# PAGE_07-DIGITAL_IO.net
KiCad netlist of a schematic drawn in Altium Designer
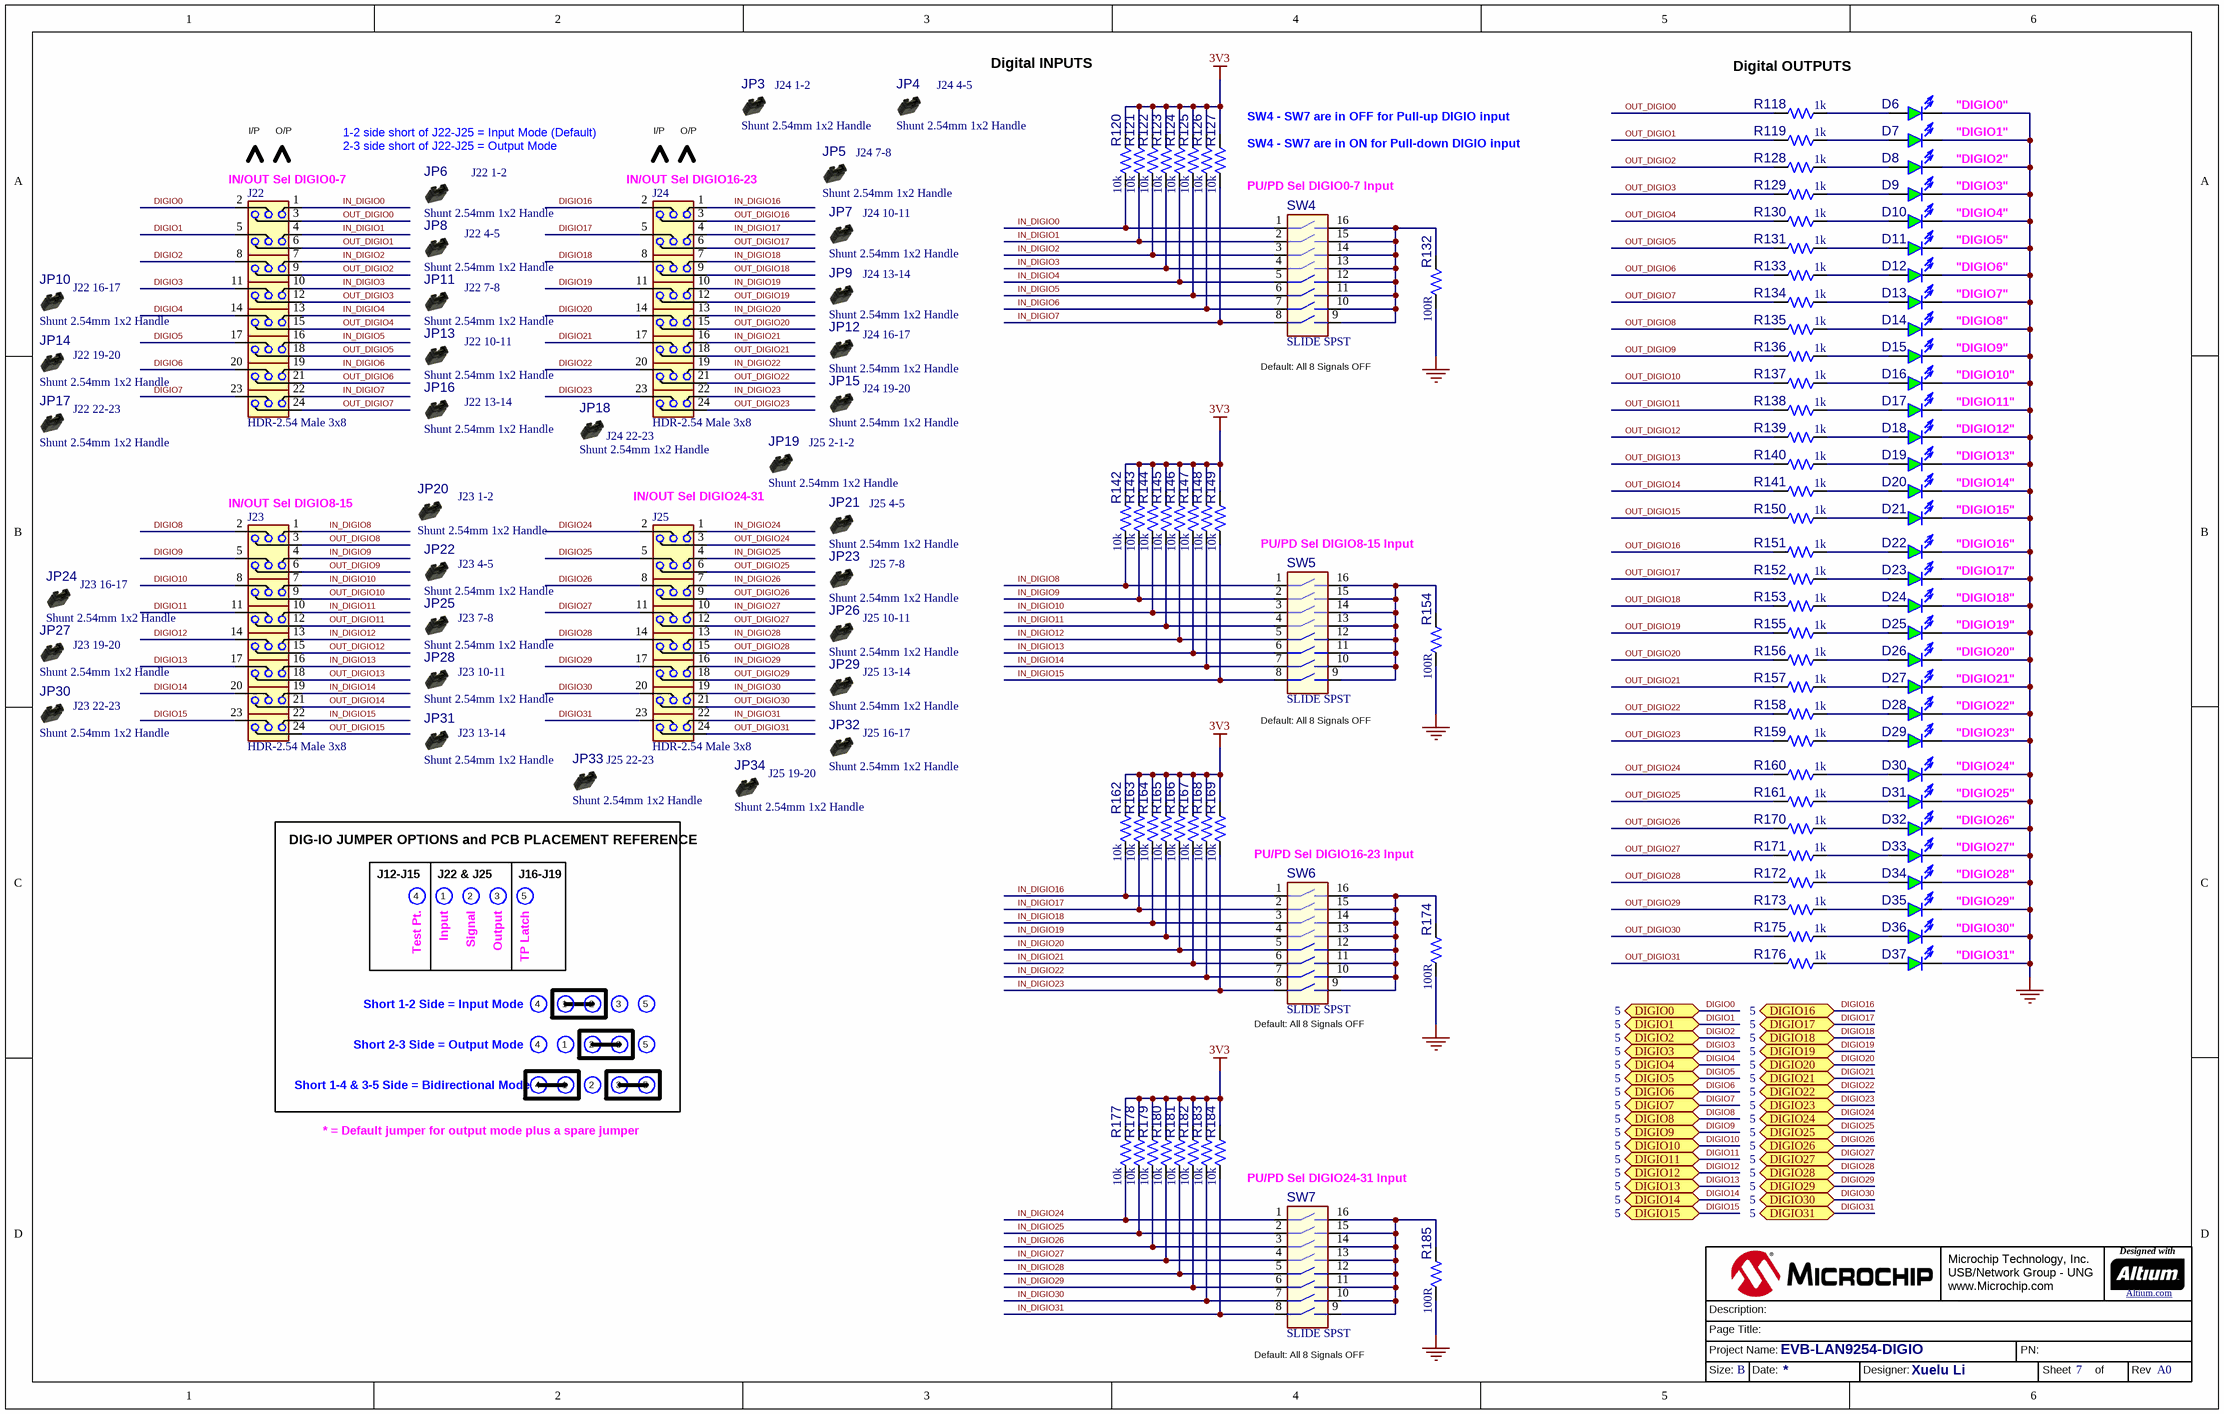
[diagram p0: PAGE 07-DIGITAL IO.SchDoc]

(export (version "E")
  (design (tool "Eeschema 10.0.6"))
  (components
    (comp (ref "D6")
      (value "LED_green")
      (footprint "LED_0603_GREEN")
      (description "LED")
      (fields (field (name "POWER") "75mW") (field (name "OWNER") "Tad Ahlvers"))
      (libsource (lib "MCHP-CDB") (part "LED_green"))
    )
    (comp (ref "D7")
      (value "LED_green")
      (footprint "LED_0603_GREEN")
      (description "LED")
      (fields (field (name "POWER") "75mW") (field (name "OWNER") "Tad Ahlvers"))
      (libsource (lib "MCHP-CDB") (part "LED_green"))
    )
    (comp (ref "D8")
      (value "LED_green")
      (footprint "LED_0603_GREEN")
      (description "LED")
      (fields (field (name "POWER") "75mW") (field (name "OWNER") "Tad Ahlvers"))
      (libsource (lib "MCHP-CDB") (part "LED_green"))
    )
    (comp (ref "D9")
      (value "LED_green")
      (footprint "LED_0603_GREEN")
      (description "LED")
      (fields (field (name "POWER") "75mW") (field (name "OWNER") "Tad Ahlvers"))
      (libsource (lib "MCHP-CDB") (part "LED_green"))
    )
    (comp (ref "D10")
      (value "LED_green")
      (footprint "LED_0603_GREEN")
      (description "LED")
      (fields (field (name "POWER") "75mW") (field (name "OWNER") "Tad Ahlvers"))
      (libsource (lib "MCHP-CDB") (part "LED_green"))
    )
    (comp (ref "D11")
      (value "LED_green")
      (footprint "LED_0603_GREEN")
      (description "LED")
      (fields (field (name "POWER") "75mW") (field (name "OWNER") "Tad Ahlvers"))
      (libsource (lib "MCHP-CDB") (part "LED_green"))
    )
    (comp (ref "D12")
      (value "LED_green")
      (footprint "LED_0603_GREEN")
      (description "LED")
      (fields (field (name "POWER") "75mW") (field (name "OWNER") "Tad Ahlvers"))
      (libsource (lib "MCHP-CDB") (part "LED_green"))
    )
    (comp (ref "D13")
      (value "LED_green")
      (footprint "LED_0603_GREEN")
      (description "LED")
      (fields (field (name "POWER") "75mW") (field (name "OWNER") "Tad Ahlvers"))
      (libsource (lib "MCHP-CDB") (part "LED_green"))
    )
    (comp (ref "D14")
      (value "LED_green")
      (footprint "LED_0603_GREEN")
      (description "LED")
      (fields (field (name "POWER") "75mW") (field (name "OWNER") "Tad Ahlvers"))
      (libsource (lib "MCHP-CDB") (part "LED_green"))
    )
    (comp (ref "D15")
      (value "LED_green")
      (footprint "LED_0603_GREEN")
      (description "LED")
      (fields (field (name "POWER") "75mW") (field (name "OWNER") "Tad Ahlvers"))
      (libsource (lib "MCHP-CDB") (part "LED_green"))
    )
    (comp (ref "D16")
      (value "LED_green")
      (footprint "LED_0603_GREEN")
      (description "LED")
      (fields (field (name "POWER") "75mW") (field (name "OWNER") "Tad Ahlvers"))
      (libsource (lib "MCHP-CDB") (part "LED_green"))
    )
    (comp (ref "D17")
      (value "LED_green")
      (footprint "LED_0603_GREEN")
      (description "LED")
      (fields (field (name "POWER") "75mW") (field (name "OWNER") "Tad Ahlvers"))
      (libsource (lib "MCHP-CDB") (part "LED_green"))
    )
    (comp (ref "D18")
      (value "LED_green")
      (footprint "LED_0603_GREEN")
      (description "LED")
      (fields (field (name "POWER") "75mW") (field (name "OWNER") "Tad Ahlvers"))
      (libsource (lib "MCHP-CDB") (part "LED_green"))
    )
    (comp (ref "D19")
      (value "LED_green")
      (footprint "LED_0603_GREEN")
      (description "LED")
      (fields (field (name "POWER") "75mW") (field (name "OWNER") "Tad Ahlvers"))
      (libsource (lib "MCHP-CDB") (part "LED_green"))
    )
    (comp (ref "D20")
      (value "LED_green")
      (footprint "LED_0603_GREEN")
      (description "LED")
      (fields (field (name "POWER") "75mW") (field (name "OWNER") "Tad Ahlvers"))
      (libsource (lib "MCHP-CDB") (part "LED_green"))
    )
    (comp (ref "D21")
      (value "LED_green")
      (footprint "LED_0603_GREEN")
      (description "LED")
      (fields (field (name "POWER") "75mW") (field (name "OWNER") "Tad Ahlvers"))
      (libsource (lib "MCHP-CDB") (part "LED_green"))
    )
    (comp (ref "D22")
      (value "LED_green")
      (footprint "LED_0603_GREEN")
      (description "LED")
      (fields (field (name "POWER") "75mW") (field (name "OWNER") "Tad Ahlvers"))
      (libsource (lib "MCHP-CDB") (part "LED_green"))
    )
    (comp (ref "D23")
      (value "LED_green")
      (footprint "LED_0603_GREEN")
      (description "LED")
      (fields (field (name "POWER") "75mW") (field (name "OWNER") "Tad Ahlvers"))
      (libsource (lib "MCHP-CDB") (part "LED_green"))
    )
    (comp (ref "D24")
      (value "LED_green")
      (footprint "LED_0603_GREEN")
      (description "LED")
      (fields (field (name "POWER") "75mW") (field (name "OWNER") "Tad Ahlvers"))
      (libsource (lib "MCHP-CDB") (part "LED_green"))
    )
    (comp (ref "D25")
      (value "LED_green")
      (footprint "LED_0603_GREEN")
      (description "LED")
      (fields (field (name "POWER") "75mW") (field (name "OWNER") "Tad Ahlvers"))
      (libsource (lib "MCHP-CDB") (part "LED_green"))
    )
    (comp (ref "D26")
      (value "LED_green")
      (footprint "LED_0603_GREEN")
      (description "LED")
      (fields (field (name "POWER") "75mW") (field (name "OWNER") "Tad Ahlvers"))
      (libsource (lib "MCHP-CDB") (part "LED_green"))
    )
    (comp (ref "D27")
      (value "LED_green")
      (footprint "LED_0603_GREEN")
      (description "LED")
      (fields (field (name "POWER") "75mW") (field (name "OWNER") "Tad Ahlvers"))
      (libsource (lib "MCHP-CDB") (part "LED_green"))
    )
    (comp (ref "D28")
      (value "LED_green")
      (footprint "LED_0603_GREEN")
      (description "LED")
      (fields (field (name "POWER") "75mW") (field (name "OWNER") "Tad Ahlvers"))
      (libsource (lib "MCHP-CDB") (part "LED_green"))
    )
    (comp (ref "D29")
      (value "LED_green")
      (footprint "LED_0603_GREEN")
      (description "LED")
      (fields (field (name "POWER") "75mW") (field (name "OWNER") "Tad Ahlvers"))
      (libsource (lib "MCHP-CDB") (part "LED_green"))
    )
    (comp (ref "D30")
      (value "LED_green")
      (footprint "LED_0603_GREEN")
      (description "LED")
      (fields (field (name "POWER") "75mW") (field (name "OWNER") "Tad Ahlvers"))
      (libsource (lib "MCHP-CDB") (part "LED_green"))
    )
    (comp (ref "D31")
      (value "LED_green")
      (footprint "LED_0603_GREEN")
      (description "LED")
      (fields (field (name "POWER") "75mW") (field (name "OWNER") "Tad Ahlvers"))
      (libsource (lib "MCHP-CDB") (part "LED_green"))
    )
    (comp (ref "D32")
      (value "LED_green")
      (footprint "LED_0603_GREEN")
      (description "LED")
      (fields (field (name "POWER") "75mW") (field (name "OWNER") "Tad Ahlvers"))
      (libsource (lib "MCHP-CDB") (part "LED_green"))
    )
    (comp (ref "D33")
      (value "LED_green")
      (footprint "LED_0603_GREEN")
      (description "LED")
      (fields (field (name "POWER") "75mW") (field (name "OWNER") "Tad Ahlvers"))
      (libsource (lib "MCHP-CDB") (part "LED_green"))
    )
    (comp (ref "D34")
      (value "LED_green")
      (footprint "LED_0603_GREEN")
      (description "LED")
      (fields (field (name "POWER") "75mW") (field (name "OWNER") "Tad Ahlvers"))
      (libsource (lib "MCHP-CDB") (part "LED_green"))
    )
    (comp (ref "D35")
      (value "LED_green")
      (footprint "LED_0603_GREEN")
      (description "LED")
      (fields (field (name "POWER") "75mW") (field (name "OWNER") "Tad Ahlvers"))
      (libsource (lib "MCHP-CDB") (part "LED_green"))
    )
    (comp (ref "D36")
      (value "LED_green")
      (footprint "LED_0603_GREEN")
      (description "LED")
      (fields (field (name "POWER") "75mW") (field (name "OWNER") "Tad Ahlvers"))
      (libsource (lib "MCHP-CDB") (part "LED_green"))
    )
    (comp (ref "D37")
      (value "LED_green")
      (footprint "LED_0603_GREEN")
      (description "LED")
      (fields (field (name "POWER") "75mW") (field (name "OWNER") "Tad Ahlvers"))
      (libsource (lib "MCHP-CDB") (part "LED_green"))
    )
    (comp (ref "J22")
      (value "HDR-2.54 Male 3x8")
      (footprint "CON_HDR_2.54_3X8-shifted1")
      (fields (field (name "Comment") "CON_HDR_2.54_3X8-shifted1") (field (name "OWNER") "Sam Charles"))
      (libsource (lib "MCHP-CDB") (part "Header 3X8"))
    )
    (comp (ref "J23")
      (value "HDR-2.54 Male 3x8")
      (footprint "CON_HDR_2.54_3X8-shifted1")
      (fields (field (name "Comment") "CON_HDR_2.54_3X8-shifted1") (field (name "OWNER") "Sam Charles"))
      (libsource (lib "MCHP-CDB") (part "Header 3X8"))
    )
    (comp (ref "J24")
      (value "HDR-2.54 Male 3x8")
      (footprint "CON_HDR_2.54_3X8-shifted1")
      (fields (field (name "Comment") "CON_HDR_2.54_3X8-shifted1") (field (name "OWNER") "Sam Charles"))
      (libsource (lib "MCHP-CDB") (part "Header 3X8"))
    )
    (comp (ref "J25")
      (value "HDR-2.54 Male 3x8")
      (footprint "CON_HDR_2.54_3X8-shifted1")
      (fields (field (name "Comment") "CON_HDR_2.54_3X8-shifted1") (field (name "OWNER") "Sam Charles"))
      (libsource (lib "MCHP-CDB") (part "Header 3X8"))
    )
    (comp (ref "JP3")
      (value "Shunt 2.54mm 1x2 Handle")
      (footprint "Jumper_W_Handle_Mechanical")
      (fields (field (name "BOM NOTES") "J24 1-2") (field (name "Comment") "Jumper Mechanical"))
      (libsource (lib "MCHP-CDB") (part "Jumper Mechanical"))
    )
    (comp (ref "JP4")
      (value "Shunt 2.54mm 1x2 Handle")
      (footprint "Jumper_W_Handle_Mechanical")
      (fields (field (name "BOM NOTES") "J24 4-5") (field (name "Comment") "Jumper Mechanical"))
      (libsource (lib "MCHP-CDB") (part "Jumper Mechanical"))
    )
    (comp (ref "JP5")
      (value "Shunt 2.54mm 1x2 Handle")
      (footprint "Jumper_W_Handle_Mechanical")
      (fields (field (name "BOM NOTES") "J24 7-8") (field (name "Comment") "Jumper Mechanical"))
      (libsource (lib "MCHP-CDB") (part "Jumper Mechanical"))
    )
    (comp (ref "JP6")
      (value "Shunt 2.54mm 1x2 Handle")
      (footprint "Jumper_W_Handle_Mechanical")
      (fields (field (name "BOM NOTES") "J22 1-2") (field (name "Comment") "Jumper Mechanical"))
      (libsource (lib "MCHP-CDB") (part "Jumper Mechanical"))
    )
    (comp (ref "JP7")
      (value "Shunt 2.54mm 1x2 Handle")
      (footprint "Jumper_W_Handle_Mechanical")
      (fields (field (name "BOM NOTES") "J24 10-11") (field (name "Comment") "Jumper Mechanical"))
      (libsource (lib "MCHP-CDB") (part "Jumper Mechanical"))
    )
    (comp (ref "JP8")
      (value "Shunt 2.54mm 1x2 Handle")
      (footprint "Jumper_W_Handle_Mechanical")
      (fields (field (name "BOM NOTES") "J22 4-5") (field (name "Comment") "Jumper Mechanical"))
      (libsource (lib "MCHP-CDB") (part "Jumper Mechanical"))
    )
    (comp (ref "JP9")
      (value "Shunt 2.54mm 1x2 Handle")
      (footprint "Jumper_W_Handle_Mechanical")
      (fields (field (name "BOM NOTES") "J24 13-14") (field (name "Comment") "Jumper Mechanical"))
      (libsource (lib "MCHP-CDB") (part "Jumper Mechanical"))
    )
    (comp (ref "JP10")
      (value "Shunt 2.54mm 1x2 Handle")
      (footprint "Jumper_W_Handle_Mechanical")
      (fields (field (name "BOM NOTES") "J22 16-17") (field (name "Comment") "Jumper Mechanical"))
      (libsource (lib "MCHP-CDB") (part "Jumper Mechanical"))
    )
    (comp (ref "JP11")
      (value "Shunt 2.54mm 1x2 Handle")
      (footprint "Jumper_W_Handle_Mechanical")
      (fields (field (name "BOM NOTES") "J22 7-8") (field (name "Comment") "Jumper Mechanical"))
      (libsource (lib "MCHP-CDB") (part "Jumper Mechanical"))
    )
    (comp (ref "JP12")
      (value "Shunt 2.54mm 1x2 Handle")
      (footprint "Jumper_W_Handle_Mechanical")
      (fields (field (name "BOM NOTES") "J24 16-17") (field (name "Comment") "Jumper Mechanical"))
      (libsource (lib "MCHP-CDB") (part "Jumper Mechanical"))
    )
    (comp (ref "JP13")
      (value "Shunt 2.54mm 1x2 Handle")
      (footprint "Jumper_W_Handle_Mechanical")
      (fields (field (name "BOM NOTES") "J22 10-11") (field (name "Comment") "Jumper Mechanical"))
      (libsource (lib "MCHP-CDB") (part "Jumper Mechanical"))
    )
    (comp (ref "JP14")
      (value "Shunt 2.54mm 1x2 Handle")
      (footprint "Jumper_W_Handle_Mechanical")
      (fields (field (name "BOM NOTES") "J22 19-20") (field (name "Comment") "Jumper Mechanical"))
      (libsource (lib "MCHP-CDB") (part "Jumper Mechanical"))
    )
    (comp (ref "JP15")
      (value "Shunt 2.54mm 1x2 Handle")
      (footprint "Jumper_W_Handle_Mechanical")
      (fields (field (name "BOM NOTES") "J24 19-20") (field (name "Comment") "Jumper Mechanical"))
      (libsource (lib "MCHP-CDB") (part "Jumper Mechanical"))
    )
    (comp (ref "JP16")
      (value "Shunt 2.54mm 1x2 Handle")
      (footprint "Jumper_W_Handle_Mechanical")
      (fields (field (name "BOM NOTES") "J22 13-14") (field (name "Comment") "Jumper Mechanical"))
      (libsource (lib "MCHP-CDB") (part "Jumper Mechanical"))
    )
    (comp (ref "JP17")
      (value "Shunt 2.54mm 1x2 Handle")
      (footprint "Jumper_W_Handle_Mechanical")
      (fields (field (name "BOM NOTES") "J22 22-23") (field (name "Comment") "Jumper Mechanical"))
      (libsource (lib "MCHP-CDB") (part "Jumper Mechanical"))
    )
    (comp (ref "JP18")
      (value "Shunt 2.54mm 1x2 Handle")
      (footprint "Jumper_W_Handle_Mechanical")
      (fields (field (name "BOM NOTES") "J24 22-23") (field (name "Comment") "Jumper Mechanical"))
      (libsource (lib "MCHP-CDB") (part "Jumper Mechanical"))
    )
    (comp (ref "JP19")
      (value "Shunt 2.54mm 1x2 Handle")
      (footprint "Jumper_W_Handle_Mechanical")
      (fields (field (name "BOM NOTES") "J25 2-1-2") (field (name "Comment") "Jumper Mechanical"))
      (libsource (lib "MCHP-CDB") (part "Jumper Mechanical"))
    )
    (comp (ref "JP20")
      (value "Shunt 2.54mm 1x2 Handle")
      (footprint "Jumper_W_Handle_Mechanical")
      (fields (field (name "BOM NOTES") "J23 1-2") (field (name "Comment") "Jumper Mechanical"))
      (libsource (lib "MCHP-CDB") (part "Jumper Mechanical"))
    )
    (comp (ref "JP21")
      (value "Shunt 2.54mm 1x2 Handle")
      (footprint "Jumper_W_Handle_Mechanical")
      (fields (field (name "BOM NOTES") "J25 4-5") (field (name "Comment") "Jumper Mechanical"))
      (libsource (lib "MCHP-CDB") (part "Jumper Mechanical"))
    )
    (comp (ref "JP22")
      (value "Shunt 2.54mm 1x2 Handle")
      (footprint "Jumper_W_Handle_Mechanical")
      (fields (field (name "BOM NOTES") "J23 4-5") (field (name "Comment") "Jumper Mechanical"))
      (libsource (lib "MCHP-CDB") (part "Jumper Mechanical"))
    )
    (comp (ref "JP23")
      (value "Shunt 2.54mm 1x2 Handle")
      (footprint "Jumper_W_Handle_Mechanical")
      (fields (field (name "BOM NOTES") "J25 7-8") (field (name "Comment") "Jumper Mechanical"))
      (libsource (lib "MCHP-CDB") (part "Jumper Mechanical"))
    )
    (comp (ref "JP24")
      (value "Shunt 2.54mm 1x2 Handle")
      (footprint "Jumper_W_Handle_Mechanical")
      (fields (field (name "BOM NOTES") "J23 16-17") (field (name "Comment") "Jumper Mechanical"))
      (libsource (lib "MCHP-CDB") (part "Jumper Mechanical"))
    )
    (comp (ref "JP25")
      (value "Shunt 2.54mm 1x2 Handle")
      (footprint "Jumper_W_Handle_Mechanical")
      (fields (field (name "BOM NOTES") "J23 7-8") (field (name "Comment") "Jumper Mechanical"))
      (libsource (lib "MCHP-CDB") (part "Jumper Mechanical"))
    )
    (comp (ref "JP26")
      (value "Shunt 2.54mm 1x2 Handle")
      (footprint "Jumper_W_Handle_Mechanical")
      (fields (field (name "BOM NOTES") "J25 10-11") (field (name "Comment") "Jumper Mechanical"))
      (libsource (lib "MCHP-CDB") (part "Jumper Mechanical"))
    )
    (comp (ref "JP27")
      (value "Shunt 2.54mm 1x2 Handle")
      (footprint "Jumper_W_Handle_Mechanical")
      (fields (field (name "BOM NOTES") "J23 19-20") (field (name "Comment") "Jumper Mechanical"))
      (libsource (lib "MCHP-CDB") (part "Jumper Mechanical"))
    )
    (comp (ref "JP28")
      (value "Shunt 2.54mm 1x2 Handle")
      (footprint "Jumper_W_Handle_Mechanical")
      (fields (field (name "BOM NOTES") "J23 10-11") (field (name "Comment") "Jumper Mechanical"))
      (libsource (lib "MCHP-CDB") (part "Jumper Mechanical"))
    )
    (comp (ref "JP29")
      (value "Shunt 2.54mm 1x2 Handle")
      (footprint "Jumper_W_Handle_Mechanical")
      (fields (field (name "BOM NOTES") "J25 13-14") (field (name "Comment") "Jumper Mechanical"))
      (libsource (lib "MCHP-CDB") (part "Jumper Mechanical"))
    )
    (comp (ref "JP30")
      (value "Shunt 2.54mm 1x2 Handle")
      (footprint "Jumper_W_Handle_Mechanical")
      (fields (field (name "BOM NOTES") "J23 22-23") (field (name "Comment") "Jumper Mechanical"))
      (libsource (lib "MCHP-CDB") (part "Jumper Mechanical"))
    )
    (comp (ref "JP31")
      (value "Shunt 2.54mm 1x2 Handle")
      (footprint "Jumper_W_Handle_Mechanical")
      (fields (field (name "BOM NOTES") "J23 13-14") (field (name "Comment") "Jumper Mechanical"))
      (libsource (lib "MCHP-CDB") (part "Jumper Mechanical"))
    )
    (comp (ref "JP32")
      (value "Shunt 2.54mm 1x2 Handle")
      (footprint "Jumper_W_Handle_Mechanical")
      (fields (field (name "BOM NOTES") "J25 16-17") (field (name "Comment") "Jumper Mechanical"))
      (libsource (lib "MCHP-CDB") (part "Jumper Mechanical"))
    )
    (comp (ref "JP33")
      (value "Shunt 2.54mm 1x2 Handle")
      (footprint "Jumper_W_Handle_Mechanical")
      (fields (field (name "BOM NOTES") "J25 22-23") (field (name "Comment") "Jumper Mechanical"))
      (libsource (lib "MCHP-CDB") (part "Jumper Mechanical"))
    )
    (comp (ref "JP34")
      (value "Shunt 2.54mm 1x2 Handle")
      (footprint "Jumper_W_Handle_Mechanical")
      (fields (field (name "BOM NOTES") "J25 19-20") (field (name "Comment") "Jumper Mechanical"))
      (libsource (lib "MCHP-CDB") (part "Jumper Mechanical"))
    )
    (comp (ref "R118")
      (value "1k")
      (footprint "RES_C_0603")
      (description "Resistor")
      (fields
        (field (name "TOLERANCE") "5%")
        (field (name "VOLTAGE") "75V")
        (field (name "OWNER") "Bogdan P (M91398)")
      )
      (libsource (lib "MCHP-CDB") (part "Resistor"))
    )
    (comp (ref "R119")
      (value "1k")
      (footprint "RES_C_0603")
      (description "Resistor")
      (fields
        (field (name "TOLERANCE") "5%")
        (field (name "VOLTAGE") "75V")
        (field (name "OWNER") "Bogdan P (M91398)")
      )
      (libsource (lib "MCHP-CDB") (part "Resistor"))
    )
    (comp (ref "R120")
      (value "10k")
      (footprint "RES_C_0603")
      (description "Resistor")
      (fields (field (name "TOLERANCE") "5%") (field (name "VOLTAGE") "75V"))
      (libsource (lib "MCHP-CDB") (part "Resistor"))
    )
    (comp (ref "R121")
      (value "10k")
      (footprint "RES_C_0603")
      (description "Resistor")
      (fields (field (name "TOLERANCE") "5%") (field (name "VOLTAGE") "75V"))
      (libsource (lib "MCHP-CDB") (part "Resistor"))
    )
    (comp (ref "R122")
      (value "10k")
      (footprint "RES_C_0603")
      (description "Resistor")
      (fields (field (name "TOLERANCE") "5%") (field (name "VOLTAGE") "75V"))
      (libsource (lib "MCHP-CDB") (part "Resistor"))
    )
    (comp (ref "R123")
      (value "10k")
      (footprint "RES_C_0603")
      (description "Resistor")
      (fields (field (name "TOLERANCE") "5%") (field (name "VOLTAGE") "75V"))
      (libsource (lib "MCHP-CDB") (part "Resistor"))
    )
    (comp (ref "R124")
      (value "10k")
      (footprint "RES_C_0603")
      (description "Resistor")
      (fields (field (name "TOLERANCE") "5%") (field (name "VOLTAGE") "75V"))
      (libsource (lib "MCHP-CDB") (part "Resistor"))
    )
    (comp (ref "R125")
      (value "10k")
      (footprint "RES_C_0603")
      (description "Resistor")
      (fields (field (name "TOLERANCE") "5%") (field (name "VOLTAGE") "75V"))
      (libsource (lib "MCHP-CDB") (part "Resistor"))
    )
    (comp (ref "R126")
      (value "10k")
      (footprint "RES_C_0603")
      (description "Resistor")
      (fields (field (name "TOLERANCE") "5%") (field (name "VOLTAGE") "75V"))
      (libsource (lib "MCHP-CDB") (part "Resistor"))
    )
    (comp (ref "R127")
      (value "10k")
      (footprint "RES_C_0603")
      (description "Resistor")
      (fields (field (name "TOLERANCE") "5%") (field (name "VOLTAGE") "75V"))
      (libsource (lib "MCHP-CDB") (part "Resistor"))
    )
    (comp (ref "R128")
      (value "1k")
      (footprint "RES_C_0603")
      (description "Resistor")
      (fields
        (field (name "TOLERANCE") "5%")
        (field (name "VOLTAGE") "75V")
        (field (name "OWNER") "Bogdan P (M91398)")
      )
      (libsource (lib "MCHP-CDB") (part "Resistor"))
    )
    (comp (ref "R129")
      (value "1k")
      (footprint "RES_C_0603")
      (description "Resistor")
      (fields
        (field (name "TOLERANCE") "5%")
        (field (name "VOLTAGE") "75V")
        (field (name "OWNER") "Bogdan P (M91398)")
      )
      (libsource (lib "MCHP-CDB") (part "Resistor"))
    )
    (comp (ref "R130")
      (value "1k")
      (footprint "RES_C_0603")
      (description "Resistor")
      (fields
        (field (name "TOLERANCE") "5%")
        (field (name "VOLTAGE") "75V")
        (field (name "OWNER") "Bogdan P (M91398)")
      )
      (libsource (lib "MCHP-CDB") (part "Resistor"))
    )
    (comp (ref "R131")
      (value "1k")
      (footprint "RES_C_0603")
      (description "Resistor")
      (fields
        (field (name "TOLERANCE") "5%")
        (field (name "VOLTAGE") "75V")
        (field (name "OWNER") "Bogdan P (M91398)")
      )
      (libsource (lib "MCHP-CDB") (part "Resistor"))
    )
    (comp (ref "R132")
      (value "100R")
      (footprint "RES_C_0603")
      (description "Resistor")
      (fields (field (name "TOLERANCE") "5%") (field (name "VOLTAGE") "50V"))
      (libsource (lib "MCHP-CDB") (part "Resistor"))
    )
    (comp (ref "R133")
      (value "1k")
      (footprint "RES_C_0603")
      (description "Resistor")
      (fields
        (field (name "TOLERANCE") "5%")
        (field (name "VOLTAGE") "75V")
        (field (name "OWNER") "Bogdan P (M91398)")
      )
      (libsource (lib "MCHP-CDB") (part "Resistor"))
    )
    (comp (ref "R134")
      (value "1k")
      (footprint "RES_C_0603")
      (description "Resistor")
      (fields
        (field (name "TOLERANCE") "5%")
        (field (name "VOLTAGE") "75V")
        (field (name "OWNER") "Bogdan P (M91398)")
      )
      (libsource (lib "MCHP-CDB") (part "Resistor"))
    )
    (comp (ref "R135")
      (value "1k")
      (footprint "RES_C_0603")
      (description "Resistor")
      (fields
        (field (name "TOLERANCE") "5%")
        (field (name "VOLTAGE") "75V")
        (field (name "OWNER") "Bogdan P (M91398)")
      )
      (libsource (lib "MCHP-CDB") (part "Resistor"))
    )
    (comp (ref "R136")
      (value "1k")
      (footprint "RES_C_0603")
      (description "Resistor")
      (fields
        (field (name "TOLERANCE") "5%")
        (field (name "VOLTAGE") "75V")
        (field (name "OWNER") "Bogdan P (M91398)")
      )
      (libsource (lib "MCHP-CDB") (part "Resistor"))
    )
    (comp (ref "R137")
      (value "1k")
      (footprint "RES_C_0603")
      (description "Resistor")
      (fields
        (field (name "TOLERANCE") "5%")
        (field (name "VOLTAGE") "75V")
        (field (name "OWNER") "Bogdan P (M91398)")
      )
      (libsource (lib "MCHP-CDB") (part "Resistor"))
    )
    (comp (ref "R138")
      (value "1k")
      (footprint "RES_C_0603")
      (description "Resistor")
      (fields
        (field (name "TOLERANCE") "5%")
        (field (name "VOLTAGE") "75V")
        (field (name "OWNER") "Bogdan P (M91398)")
      )
      (libsource (lib "MCHP-CDB") (part "Resistor"))
    )
    (comp (ref "R139")
      (value "1k")
      (footprint "RES_C_0603")
      (description "Resistor")
      (fields
        (field (name "TOLERANCE") "5%")
        (field (name "VOLTAGE") "75V")
        (field (name "OWNER") "Bogdan P (M91398)")
      )
      (libsource (lib "MCHP-CDB") (part "Resistor"))
    )
    (comp (ref "R140")
      (value "1k")
      (footprint "RES_C_0603")
      (description "Resistor")
      (fields
        (field (name "TOLERANCE") "5%")
        (field (name "VOLTAGE") "75V")
        (field (name "OWNER") "Bogdan P (M91398)")
      )
      (libsource (lib "MCHP-CDB") (part "Resistor"))
    )
    (comp (ref "R141")
      (value "1k")
      (footprint "RES_C_0603")
      (description "Resistor")
      (fields
        (field (name "TOLERANCE") "5%")
        (field (name "VOLTAGE") "75V")
        (field (name "OWNER") "Bogdan P (M91398)")
      )
      (libsource (lib "MCHP-CDB") (part "Resistor"))
    )
    (comp (ref "R142")
      (value "10k")
      (footprint "RES_C_0603")
      (description "Resistor")
      (fields (field (name "TOLERANCE") "5%") (field (name "VOLTAGE") "75V"))
      (libsource (lib "MCHP-CDB") (part "Resistor"))
    )
    (comp (ref "R143")
      (value "10k")
      (footprint "RES_C_0603")
      (description "Resistor")
      (fields (field (name "TOLERANCE") "5%") (field (name "VOLTAGE") "75V"))
      (libsource (lib "MCHP-CDB") (part "Resistor"))
    )
    (comp (ref "R144")
      (value "10k")
      (footprint "RES_C_0603")
      (description "Resistor")
      (fields (field (name "TOLERANCE") "5%") (field (name "VOLTAGE") "75V"))
      (libsource (lib "MCHP-CDB") (part "Resistor"))
    )
    (comp (ref "R145")
      (value "10k")
      (footprint "RES_C_0603")
      (description "Resistor")
      (fields (field (name "TOLERANCE") "5%") (field (name "VOLTAGE") "75V"))
      (libsource (lib "MCHP-CDB") (part "Resistor"))
    )
    (comp (ref "R146")
      (value "10k")
      (footprint "RES_C_0603")
      (description "Resistor")
      (fields (field (name "TOLERANCE") "5%") (field (name "VOLTAGE") "75V"))
      (libsource (lib "MCHP-CDB") (part "Resistor"))
    )
    (comp (ref "R147")
      (value "10k")
      (footprint "RES_C_0603")
      (description "Resistor")
      (fields (field (name "TOLERANCE") "5%") (field (name "VOLTAGE") "75V"))
      (libsource (lib "MCHP-CDB") (part "Resistor"))
    )
    (comp (ref "R148")
      (value "10k")
      (footprint "RES_C_0603")
      (description "Resistor")
      (fields (field (name "TOLERANCE") "5%") (field (name "VOLTAGE") "75V"))
      (libsource (lib "MCHP-CDB") (part "Resistor"))
    )
    (comp (ref "R149")
      (value "10k")
      (footprint "RES_C_0603")
      (description "Resistor")
      (fields (field (name "TOLERANCE") "5%") (field (name "VOLTAGE") "75V"))
      (libsource (lib "MCHP-CDB") (part "Resistor"))
    )
    (comp (ref "R150")
      (value "1k")
      (footprint "RES_C_0603")
      (description "Resistor")
      (fields
        (field (name "TOLERANCE") "5%")
        (field (name "VOLTAGE") "75V")
        (field (name "OWNER") "Bogdan P (M91398)")
      )
      (libsource (lib "MCHP-CDB") (part "Resistor"))
    )
    (comp (ref "R151")
      (value "1k")
      (footprint "RES_C_0603")
      (description "Resistor")
      (fields
        (field (name "TOLERANCE") "5%")
        (field (name "VOLTAGE") "75V")
        (field (name "OWNER") "Bogdan P (M91398)")
      )
      (libsource (lib "MCHP-CDB") (part "Resistor"))
    )
    (comp (ref "R152")
      (value "1k")
      (footprint "RES_C_0603")
      (description "Resistor")
      (fields
        (field (name "TOLERANCE") "5%")
        (field (name "VOLTAGE") "75V")
        (field (name "OWNER") "Bogdan P (M91398)")
      )
      (libsource (lib "MCHP-CDB") (part "Resistor"))
    )
    (comp (ref "R153")
      (value "1k")
      (footprint "RES_C_0603")
      (description "Resistor")
      (fields
        (field (name "TOLERANCE") "5%")
        (field (name "VOLTAGE") "75V")
        (field (name "OWNER") "Bogdan P (M91398)")
      )
      (libsource (lib "MCHP-CDB") (part "Resistor"))
    )
    (comp (ref "R154")
      (value "100R")
      (footprint "RES_C_0603")
      (description "Resistor")
      (fields (field (name "TOLERANCE") "5%") (field (name "VOLTAGE") "50V"))
      (libsource (lib "MCHP-CDB") (part "Resistor"))
    )
    (comp (ref "R155")
      (value "1k")
      (footprint "RES_C_0603")
      (description "Resistor")
      (fields
        (field (name "TOLERANCE") "5%")
        (field (name "VOLTAGE") "75V")
        (field (name "OWNER") "Bogdan P (M91398)")
      )
      (libsource (lib "MCHP-CDB") (part "Resistor"))
    )
    (comp (ref "R156")
      (value "1k")
      (footprint "RES_C_0603")
      (description "Resistor")
      (fields
        (field (name "TOLERANCE") "5%")
        (field (name "VOLTAGE") "75V")
        (field (name "OWNER") "Bogdan P (M91398)")
      )
      (libsource (lib "MCHP-CDB") (part "Resistor"))
    )
    (comp (ref "R157")
      (value "1k")
      (footprint "RES_C_0603")
      (description "Resistor")
      (fields
        (field (name "TOLERANCE") "5%")
        (field (name "VOLTAGE") "75V")
        (field (name "OWNER") "Bogdan P (M91398)")
      )
      (libsource (lib "MCHP-CDB") (part "Resistor"))
    )
    (comp (ref "R158")
      (value "1k")
      (footprint "RES_C_0603")
      (description "Resistor")
      (fields
        (field (name "TOLERANCE") "5%")
        (field (name "VOLTAGE") "75V")
        (field (name "OWNER") "Bogdan P (M91398)")
      )
      (libsource (lib "MCHP-CDB") (part "Resistor"))
    )
    (comp (ref "R159")
      (value "1k")
      (footprint "RES_C_0603")
      (description "Resistor")
      (fields
        (field (name "TOLERANCE") "5%")
        (field (name "VOLTAGE") "75V")
        (field (name "OWNER") "Bogdan P (M91398)")
      )
      (libsource (lib "MCHP-CDB") (part "Resistor"))
    )
    (comp (ref "R160")
      (value "1k")
      (footprint "RES_C_0603")
      (description "Resistor")
      (fields
        (field (name "TOLERANCE") "5%")
        (field (name "VOLTAGE") "75V")
        (field (name "OWNER") "Bogdan P (M91398)")
      )
      (libsource (lib "MCHP-CDB") (part "Resistor"))
    )
    (comp (ref "R161")
      (value "1k")
      (footprint "RES_C_0603")
      (description "Resistor")
      (fields
        (field (name "TOLERANCE") "5%")
        (field (name "VOLTAGE") "75V")
        (field (name "OWNER") "Bogdan P (M91398)")
      )
      (libsource (lib "MCHP-CDB") (part "Resistor"))
    )
    (comp (ref "R162")
      (value "10k")
      (footprint "RES_C_0603")
      (description "Resistor")
      (fields (field (name "TOLERANCE") "5%") (field (name "VOLTAGE") "75V"))
      (libsource (lib "MCHP-CDB") (part "Resistor"))
    )
    (comp (ref "R163")
      (value "10k")
      (footprint "RES_C_0603")
      (description "Resistor")
      (fields (field (name "TOLERANCE") "5%") (field (name "VOLTAGE") "75V"))
      (libsource (lib "MCHP-CDB") (part "Resistor"))
    )
    (comp (ref "R164")
      (value "10k")
      (footprint "RES_C_0603")
      (description "Resistor")
      (fields (field (name "TOLERANCE") "5%") (field (name "VOLTAGE") "75V"))
      (libsource (lib "MCHP-CDB") (part "Resistor"))
    )
    (comp (ref "R165")
      (value "10k")
      (footprint "RES_C_0603")
      (description "Resistor")
      (fields (field (name "TOLERANCE") "5%") (field (name "VOLTAGE") "75V"))
      (libsource (lib "MCHP-CDB") (part "Resistor"))
    )
    (comp (ref "R166")
      (value "10k")
      (footprint "RES_C_0603")
      (description "Resistor")
      (fields (field (name "TOLERANCE") "5%") (field (name "VOLTAGE") "75V"))
      (libsource (lib "MCHP-CDB") (part "Resistor"))
    )
    (comp (ref "R167")
      (value "10k")
      (footprint "RES_C_0603")
      (description "Resistor")
      (fields (field (name "TOLERANCE") "5%") (field (name "VOLTAGE") "75V"))
      (libsource (lib "MCHP-CDB") (part "Resistor"))
    )
    (comp (ref "R168")
      (value "10k")
      (footprint "RES_C_0603")
      (description "Resistor")
      (fields (field (name "TOLERANCE") "5%") (field (name "VOLTAGE") "75V"))
      (libsource (lib "MCHP-CDB") (part "Resistor"))
    )
    (comp (ref "R169")
      (value "10k")
      (footprint "RES_C_0603")
      (description "Resistor")
      (fields (field (name "TOLERANCE") "5%") (field (name "VOLTAGE") "75V"))
      (libsource (lib "MCHP-CDB") (part "Resistor"))
    )
    (comp (ref "R170")
      (value "1k")
      (footprint "RES_C_0603")
      (description "Resistor")
      (fields
        (field (name "TOLERANCE") "5%")
        (field (name "VOLTAGE") "75V")
        (field (name "OWNER") "Bogdan P (M91398)")
      )
      (libsource (lib "MCHP-CDB") (part "Resistor"))
    )
    (comp (ref "R171")
      (value "1k")
      (footprint "RES_C_0603")
      (description "Resistor")
      (fields
        (field (name "TOLERANCE") "5%")
        (field (name "VOLTAGE") "75V")
        (field (name "OWNER") "Bogdan P (M91398)")
      )
      (libsource (lib "MCHP-CDB") (part "Resistor"))
    )
    (comp (ref "R172")
      (value "1k")
      (footprint "RES_C_0603")
      (description "Resistor")
      (fields
        (field (name "TOLERANCE") "5%")
        (field (name "VOLTAGE") "75V")
        (field (name "OWNER") "Bogdan P (M91398)")
      )
      (libsource (lib "MCHP-CDB") (part "Resistor"))
    )
    (comp (ref "R173")
      (value "1k")
      (footprint "RES_C_0603")
      (description "Resistor")
      (fields
        (field (name "TOLERANCE") "5%")
        (field (name "VOLTAGE") "75V")
        (field (name "OWNER") "Bogdan P (M91398)")
      )
      (libsource (lib "MCHP-CDB") (part "Resistor"))
    )
    (comp (ref "R174")
      (value "100R")
      (footprint "RES_C_0603")
      (description "Resistor")
      (fields (field (name "TOLERANCE") "5%") (field (name "VOLTAGE") "50V"))
      (libsource (lib "MCHP-CDB") (part "Resistor"))
    )
    (comp (ref "R175")
      (value "1k")
      (footprint "RES_C_0603")
      (description "Resistor")
      (fields
        (field (name "TOLERANCE") "5%")
        (field (name "VOLTAGE") "75V")
        (field (name "OWNER") "Bogdan P (M91398)")
      )
      (libsource (lib "MCHP-CDB") (part "Resistor"))
    )
    (comp (ref "R176")
      (value "1k")
      (footprint "RES_C_0603")
      (description "Resistor")
      (fields
        (field (name "TOLERANCE") "5%")
        (field (name "VOLTAGE") "75V")
        (field (name "OWNER") "Bogdan P (M91398)")
      )
      (libsource (lib "MCHP-CDB") (part "Resistor"))
    )
    (comp (ref "R177")
      (value "10k")
      (footprint "RES_C_0603")
      (description "Resistor")
      (fields (field (name "TOLERANCE") "5%") (field (name "VOLTAGE") "75V"))
      (libsource (lib "MCHP-CDB") (part "Resistor"))
    )
    (comp (ref "R178")
      (value "10k")
      (footprint "RES_C_0603")
      (description "Resistor")
      (fields (field (name "TOLERANCE") "5%") (field (name "VOLTAGE") "75V"))
      (libsource (lib "MCHP-CDB") (part "Resistor"))
    )
    (comp (ref "R179")
      (value "10k")
      (footprint "RES_C_0603")
      (description "Resistor")
      (fields (field (name "TOLERANCE") "5%") (field (name "VOLTAGE") "75V"))
      (libsource (lib "MCHP-CDB") (part "Resistor"))
    )
    (comp (ref "R180")
      (value "10k")
      (footprint "RES_C_0603")
      (description "Resistor")
      (fields (field (name "TOLERANCE") "5%") (field (name "VOLTAGE") "75V"))
      (libsource (lib "MCHP-CDB") (part "Resistor"))
    )
    (comp (ref "R181")
      (value "10k")
      (footprint "RES_C_0603")
      (description "Resistor")
      (fields (field (name "TOLERANCE") "5%") (field (name "VOLTAGE") "75V"))
      (libsource (lib "MCHP-CDB") (part "Resistor"))
    )
    (comp (ref "R182")
      (value "10k")
      (footprint "RES_C_0603")
      (description "Resistor")
      (fields (field (name "TOLERANCE") "5%") (field (name "VOLTAGE") "75V"))
      (libsource (lib "MCHP-CDB") (part "Resistor"))
    )
    (comp (ref "R183")
      (value "10k")
      (footprint "RES_C_0603")
      (description "Resistor")
      (fields (field (name "TOLERANCE") "5%") (field (name "VOLTAGE") "75V"))
      (libsource (lib "MCHP-CDB") (part "Resistor"))
    )
    (comp (ref "R184")
      (value "10k")
      (footprint "RES_C_0603")
      (description "Resistor")
      (fields (field (name "TOLERANCE") "5%") (field (name "VOLTAGE") "75V"))
      (libsource (lib "MCHP-CDB") (part "Resistor"))
    )
    (comp (ref "R185")
      (value "100R")
      (footprint "RES_C_0603")
      (description "Resistor")
      (fields (field (name "TOLERANCE") "5%") (field (name "VOLTAGE") "50V"))
      (libsource (lib "MCHP-CDB") (part "Resistor"))
    )
    (comp (ref "SW4")
      (value "SLIDE SPST")
      (footprint "SW_SLIDE_SMD_TE_1-1825058-9")
      (fields
        (field (name "VOLTAGE") "24V")
        (field (name "Comment") "SWITCH DIP 8 SPST")
        (field (name "OWNER") "Sam Charles")
      )
      (libsource (lib "MCHP-CDB") (part "SWITCH DIP 8 SPST"))
    )
    (comp (ref "SW5")
      (value "SLIDE SPST")
      (footprint "SW_SLIDE_SMD_TE_1-1825058-9")
      (fields
        (field (name "VOLTAGE") "24V")
        (field (name "Comment") "SWITCH DIP 8 SPST")
        (field (name "OWNER") "Sam Charles")
      )
      (libsource (lib "MCHP-CDB") (part "SWITCH DIP 8 SPST"))
    )
    (comp (ref "SW6")
      (value "SLIDE SPST")
      (footprint "SW_SLIDE_SMD_TE_1-1825058-9")
      (fields
        (field (name "VOLTAGE") "24V")
        (field (name "Comment") "SWITCH DIP 8 SPST")
        (field (name "OWNER") "Sam Charles")
      )
      (libsource (lib "MCHP-CDB") (part "SWITCH DIP 8 SPST"))
    )
    (comp (ref "SW7")
      (value "SLIDE SPST")
      (footprint "SW_SLIDE_SMD_TE_1-1825058-9")
      (fields
        (field (name "VOLTAGE") "24V")
        (field (name "Comment") "SWITCH DIP 8 SPST")
        (field (name "OWNER") "Sam Charles")
      )
      (libsource (lib "MCHP-CDB") (part "SWITCH DIP 8 SPST"))
    )
  )
  (nets
    (net (code "1") (name "/DIGIO0") (class "Default")
      (node (ref "J22") (pin "2") (pinfunction "P2_2") (pintype "passive"))
    )
    (net (code "2") (name "/DIGIO1") (class "Default")
      (node (ref "J22") (pin "5") (pinfunction "P5_5") (pintype "passive"))
    )
    (net (code "3") (name "/DIGIO2") (class "Default")
      (node (ref "J22") (pin "8") (pinfunction "P8_8") (pintype "passive"))
    )
    (net (code "4") (name "/DIGIO3") (class "Default")
      (node (ref "J22") (pin "11") (pinfunction "P11_11") (pintype "passive"))
    )
    (net (code "5") (name "/DIGIO4") (class "Default")
      (node (ref "J22") (pin "14") (pinfunction "P14_14") (pintype "passive"))
    )
    (net (code "6") (name "/DIGIO5") (class "Default")
      (node (ref "J22") (pin "17") (pinfunction "P17_17") (pintype "passive"))
    )
    (net (code "7") (name "/DIGIO6") (class "Default")
      (node (ref "J22") (pin "20") (pinfunction "P20_20") (pintype "passive"))
    )
    (net (code "8") (name "/DIGIO7") (class "Default")
      (node (ref "J22") (pin "23") (pinfunction "P23_23") (pintype "passive"))
    )
    (net (code "9") (name "/DIGIO8") (class "Default")
      (node (ref "J23") (pin "2") (pinfunction "P2_2") (pintype "passive"))
    )
    (net (code "10") (name "/DIGIO9") (class "Default")
      (node (ref "J23") (pin "5") (pinfunction "P5_5") (pintype "passive"))
    )
    (net (code "11") (name "/DIGIO10") (class "Default")
      (node (ref "J23") (pin "8") (pinfunction "P8_8") (pintype "passive"))
    )
    (net (code "12") (name "/DIGIO11") (class "Default")
      (node (ref "J23") (pin "11") (pinfunction "P11_11") (pintype "passive"))
    )
    (net (code "13") (name "/DIGIO12") (class "Default")
      (node (ref "J23") (pin "14") (pinfunction "P14_14") (pintype "passive"))
    )
    (net (code "14") (name "/DIGIO13") (class "Default")
      (node (ref "J23") (pin "17") (pinfunction "P17_17") (pintype "passive"))
    )
    (net (code "15") (name "/DIGIO14") (class "Default")
      (node (ref "J23") (pin "20") (pinfunction "P20_20") (pintype "passive"))
    )
    (net (code "16") (name "/DIGIO15") (class "Default")
      (node (ref "J23") (pin "23") (pinfunction "P23_23") (pintype "passive"))
    )
    (net (code "17") (name "/DIGIO16") (class "Default")
      (node (ref "J24") (pin "2") (pinfunction "P2_2") (pintype "passive"))
    )
    (net (code "18") (name "/DIGIO17") (class "Default")
      (node (ref "J24") (pin "5") (pinfunction "P5_5") (pintype "passive"))
    )
    (net (code "19") (name "/DIGIO18") (class "Default")
      (node (ref "J24") (pin "8") (pinfunction "P8_8") (pintype "passive"))
    )
    (net (code "20") (name "/DIGIO19") (class "Default")
      (node (ref "J24") (pin "11") (pinfunction "P11_11") (pintype "passive"))
    )
    (net (code "21") (name "/DIGIO20") (class "Default")
      (node (ref "J24") (pin "14") (pinfunction "P14_14") (pintype "passive"))
    )
    (net (code "22") (name "/DIGIO21") (class "Default")
      (node (ref "J24") (pin "17") (pinfunction "P17_17") (pintype "passive"))
    )
    (net (code "23") (name "/DIGIO22") (class "Default")
      (node (ref "J24") (pin "20") (pinfunction "P20_20") (pintype "passive"))
    )
    (net (code "24") (name "/DIGIO23") (class "Default")
      (node (ref "J24") (pin "23") (pinfunction "P23_23") (pintype "passive"))
    )
    (net (code "25") (name "/DIGIO24") (class "Default")
      (node (ref "J25") (pin "2") (pinfunction "P2_2") (pintype "passive"))
    )
    (net (code "26") (name "/DIGIO25") (class "Default")
      (node (ref "J25") (pin "5") (pinfunction "P5_5") (pintype "passive"))
    )
    (net (code "27") (name "/DIGIO26") (class "Default")
      (node (ref "J25") (pin "8") (pinfunction "P8_8") (pintype "passive"))
    )
    (net (code "28") (name "/DIGIO27") (class "Default")
      (node (ref "J25") (pin "11") (pinfunction "P11_11") (pintype "passive"))
    )
    (net (code "29") (name "/DIGIO28") (class "Default")
      (node (ref "J25") (pin "14") (pinfunction "P14_14") (pintype "passive"))
    )
    (net (code "30") (name "/DIGIO29") (class "Default")
      (node (ref "J25") (pin "17") (pinfunction "P17_17") (pintype "passive"))
    )
    (net (code "31") (name "/DIGIO30") (class "Default")
      (node (ref "J25") (pin "20") (pinfunction "P20_20") (pintype "passive"))
    )
    (net (code "32") (name "/DIGIO31") (class "Default")
      (node (ref "J25") (pin "23") (pinfunction "P23_23") (pintype "passive"))
    )
    (net (code "33") (name "/IN_DIGIO0") (class "Default")
      (node (ref "J22") (pin "1") (pinfunction "P1_1") (pintype "passive"))
      (node (ref "R120") (pin "1") (pinfunction "1_1") (pintype "passive"))
      (node (ref "SW4") (pin "1") (pinfunction "1_1") (pintype "passive"))
    )
    (net (code "34") (name "/IN_DIGIO1") (class "Default")
      (node (ref "J22") (pin "4") (pinfunction "P4_4") (pintype "passive"))
      (node (ref "R121") (pin "1") (pinfunction "1_1") (pintype "passive"))
      (node (ref "SW4") (pin "2") (pinfunction "2_2") (pintype "passive"))
    )
    (net (code "35") (name "/IN_DIGIO2") (class "Default")
      (node (ref "J22") (pin "7") (pinfunction "P7_7") (pintype "passive"))
      (node (ref "R122") (pin "1") (pinfunction "1_1") (pintype "passive"))
      (node (ref "SW4") (pin "3") (pinfunction "3_3") (pintype "passive"))
    )
    (net (code "36") (name "/IN_DIGIO3") (class "Default")
      (node (ref "J22") (pin "10") (pinfunction "P10_10") (pintype "passive"))
      (node (ref "R123") (pin "1") (pinfunction "1_1") (pintype "passive"))
      (node (ref "SW4") (pin "4") (pinfunction "4_4") (pintype "passive"))
    )
    (net (code "37") (name "/IN_DIGIO4") (class "Default")
      (node (ref "J22") (pin "13") (pinfunction "P13_13") (pintype "passive"))
      (node (ref "R124") (pin "1") (pinfunction "1_1") (pintype "passive"))
      (node (ref "SW4") (pin "5") (pinfunction "5_5") (pintype "passive"))
    )
    (net (code "38") (name "/IN_DIGIO5") (class "Default")
      (node (ref "J22") (pin "16") (pinfunction "P16_16") (pintype "passive"))
      (node (ref "R125") (pin "1") (pinfunction "1_1") (pintype "passive"))
      (node (ref "SW4") (pin "6") (pinfunction "6_6") (pintype "passive"))
    )
    (net (code "39") (name "/IN_DIGIO6") (class "Default")
      (node (ref "J22") (pin "19") (pinfunction "P19_19") (pintype "passive"))
      (node (ref "R126") (pin "1") (pinfunction "1_1") (pintype "passive"))
      (node (ref "SW4") (pin "7") (pinfunction "7_7") (pintype "passive"))
    )
    (net (code "40") (name "/IN_DIGIO7") (class "Default")
      (node (ref "J22") (pin "22") (pinfunction "P22_22") (pintype "passive"))
      (node (ref "R127") (pin "1") (pinfunction "1_1") (pintype "passive"))
      (node (ref "SW4") (pin "8") (pinfunction "8_8") (pintype "passive"))
    )
    (net (code "41") (name "/IN_DIGIO8") (class "Default")
      (node (ref "J23") (pin "1") (pinfunction "P1_1") (pintype "passive"))
      (node (ref "R142") (pin "1") (pinfunction "1_1") (pintype "passive"))
      (node (ref "SW5") (pin "1") (pinfunction "1_1") (pintype "passive"))
    )
    (net (code "42") (name "/IN_DIGIO9") (class "Default")
      (node (ref "J23") (pin "4") (pinfunction "P4_4") (pintype "passive"))
      (node (ref "R143") (pin "1") (pinfunction "1_1") (pintype "passive"))
      (node (ref "SW5") (pin "2") (pinfunction "2_2") (pintype "passive"))
    )
    (net (code "43") (name "/IN_DIGIO10") (class "Default")
      (node (ref "J23") (pin "7") (pinfunction "P7_7") (pintype "passive"))
      (node (ref "R144") (pin "1") (pinfunction "1_1") (pintype "passive"))
      (node (ref "SW5") (pin "3") (pinfunction "3_3") (pintype "passive"))
    )
    (net (code "44") (name "/IN_DIGIO11") (class "Default")
      (node (ref "J23") (pin "10") (pinfunction "P10_10") (pintype "passive"))
      (node (ref "R145") (pin "1") (pinfunction "1_1") (pintype "passive"))
      (node (ref "SW5") (pin "4") (pinfunction "4_4") (pintype "passive"))
    )
    (net (code "45") (name "/IN_DIGIO12") (class "Default")
      (node (ref "J23") (pin "13") (pinfunction "P13_13") (pintype "passive"))
      (node (ref "R146") (pin "1") (pinfunction "1_1") (pintype "passive"))
      (node (ref "SW5") (pin "5") (pinfunction "5_5") (pintype "passive"))
    )
    (net (code "46") (name "/IN_DIGIO13") (class "Default")
      (node (ref "J23") (pin "16") (pinfunction "P16_16") (pintype "passive"))
      (node (ref "R147") (pin "1") (pinfunction "1_1") (pintype "passive"))
      (node (ref "SW5") (pin "6") (pinfunction "6_6") (pintype "passive"))
    )
    (net (code "47") (name "/IN_DIGIO14") (class "Default")
      (node (ref "J23") (pin "19") (pinfunction "P19_19") (pintype "passive"))
      (node (ref "R148") (pin "1") (pinfunction "1_1") (pintype "passive"))
      (node (ref "SW5") (pin "7") (pinfunction "7_7") (pintype "passive"))
    )
    (net (code "48") (name "/IN_DIGIO15") (class "Default")
      (node (ref "J23") (pin "22") (pinfunction "P22_22") (pintype "passive"))
      (node (ref "R149") (pin "1") (pinfunction "1_1") (pintype "passive"))
      (node (ref "SW5") (pin "8") (pinfunction "8_8") (pintype "passive"))
    )
    (net (code "49") (name "/IN_DIGIO16") (class "Default")
      (node (ref "J24") (pin "1") (pinfunction "P1_1") (pintype "passive"))
      (node (ref "R162") (pin "1") (pinfunction "1_1") (pintype "passive"))
      (node (ref "SW6") (pin "1") (pinfunction "1_1") (pintype "passive"))
    )
    (net (code "50") (name "/IN_DIGIO17") (class "Default")
      (node (ref "J24") (pin "4") (pinfunction "P4_4") (pintype "passive"))
      (node (ref "R163") (pin "1") (pinfunction "1_1") (pintype "passive"))
      (node (ref "SW6") (pin "2") (pinfunction "2_2") (pintype "passive"))
    )
    (net (code "51") (name "/IN_DIGIO18") (class "Default")
      (node (ref "J24") (pin "7") (pinfunction "P7_7") (pintype "passive"))
      (node (ref "R164") (pin "1") (pinfunction "1_1") (pintype "passive"))
      (node (ref "SW6") (pin "3") (pinfunction "3_3") (pintype "passive"))
    )
    (net (code "52") (name "/IN_DIGIO19") (class "Default")
      (node (ref "J24") (pin "10") (pinfunction "P10_10") (pintype "passive"))
      (node (ref "R165") (pin "1") (pinfunction "1_1") (pintype "passive"))
      (node (ref "SW6") (pin "4") (pinfunction "4_4") (pintype "passive"))
    )
    (net (code "53") (name "/IN_DIGIO20") (class "Default")
      (node (ref "J24") (pin "13") (pinfunction "P13_13") (pintype "passive"))
      (node (ref "R166") (pin "1") (pinfunction "1_1") (pintype "passive"))
      (node (ref "SW6") (pin "5") (pinfunction "5_5") (pintype "passive"))
    )
    (net (code "54") (name "/IN_DIGIO21") (class "Default")
      (node (ref "J24") (pin "16") (pinfunction "P16_16") (pintype "passive"))
      (node (ref "R167") (pin "1") (pinfunction "1_1") (pintype "passive"))
      (node (ref "SW6") (pin "6") (pinfunction "6_6") (pintype "passive"))
    )
    (net (code "55") (name "/IN_DIGIO22") (class "Default")
      (node (ref "J24") (pin "19") (pinfunction "P19_19") (pintype "passive"))
      (node (ref "R168") (pin "1") (pinfunction "1_1") (pintype "passive"))
      (node (ref "SW6") (pin "7") (pinfunction "7_7") (pintype "passive"))
    )
    (net (code "56") (name "/IN_DIGIO23") (class "Default")
      (node (ref "J24") (pin "22") (pinfunction "P22_22") (pintype "passive"))
      (node (ref "R169") (pin "1") (pinfunction "1_1") (pintype "passive"))
      (node (ref "SW6") (pin "8") (pinfunction "8_8") (pintype "passive"))
    )
    (net (code "57") (name "/IN_DIGIO24") (class "Default")
      (node (ref "J25") (pin "1") (pinfunction "P1_1") (pintype "passive"))
      (node (ref "R177") (pin "1") (pinfunction "1_1") (pintype "passive"))
      (node (ref "SW7") (pin "1") (pinfunction "1_1") (pintype "passive"))
    )
    (net (code "58") (name "/IN_DIGIO25") (class "Default")
      (node (ref "J25") (pin "4") (pinfunction "P4_4") (pintype "passive"))
      (node (ref "R178") (pin "1") (pinfunction "1_1") (pintype "passive"))
      (node (ref "SW7") (pin "2") (pinfunction "2_2") (pintype "passive"))
    )
    (net (code "59") (name "/IN_DIGIO26") (class "Default")
      (node (ref "J25") (pin "7") (pinfunction "P7_7") (pintype "passive"))
      (node (ref "R179") (pin "1") (pinfunction "1_1") (pintype "passive"))
      (node (ref "SW7") (pin "3") (pinfunction "3_3") (pintype "passive"))
    )
    (net (code "60") (name "/IN_DIGIO27") (class "Default")
      (node (ref "J25") (pin "10") (pinfunction "P10_10") (pintype "passive"))
      (node (ref "R180") (pin "1") (pinfunction "1_1") (pintype "passive"))
      (node (ref "SW7") (pin "4") (pinfunction "4_4") (pintype "passive"))
    )
    (net (code "61") (name "/IN_DIGIO28") (class "Default")
      (node (ref "J25") (pin "13") (pinfunction "P13_13") (pintype "passive"))
      (node (ref "R181") (pin "1") (pinfunction "1_1") (pintype "passive"))
      (node (ref "SW7") (pin "5") (pinfunction "5_5") (pintype "passive"))
    )
    (net (code "62") (name "/IN_DIGIO29") (class "Default")
      (node (ref "J25") (pin "16") (pinfunction "P16_16") (pintype "passive"))
      (node (ref "R182") (pin "1") (pinfunction "1_1") (pintype "passive"))
      (node (ref "SW7") (pin "6") (pinfunction "6_6") (pintype "passive"))
    )
    (net (code "63") (name "/IN_DIGIO30") (class "Default")
      (node (ref "J25") (pin "19") (pinfunction "P19_19") (pintype "passive"))
      (node (ref "R183") (pin "1") (pinfunction "1_1") (pintype "passive"))
      (node (ref "SW7") (pin "7") (pinfunction "7_7") (pintype "passive"))
    )
    (net (code "64") (name "/IN_DIGIO31") (class "Default")
      (node (ref "J25") (pin "22") (pinfunction "P22_22") (pintype "passive"))
      (node (ref "R184") (pin "1") (pinfunction "1_1") (pintype "passive"))
      (node (ref "SW7") (pin "8") (pinfunction "8_8") (pintype "passive"))
    )
    (net (code "65") (name "/OUT_DIGIO0") (class "Default")
      (node (ref "J22") (pin "3") (pinfunction "3_3") (pintype "passive"))
      (node (ref "R118") (pin "1") (pinfunction "1_1") (pintype "passive"))
    )
    (net (code "66") (name "/OUT_DIGIO1") (class "Default")
      (node (ref "J22") (pin "6") (pinfunction "P6_6") (pintype "passive"))
      (node (ref "R119") (pin "1") (pinfunction "1_1") (pintype "passive"))
    )
    (net (code "67") (name "/OUT_DIGIO2") (class "Default")
      (node (ref "J22") (pin "9") (pinfunction "P9_9") (pintype "passive"))
      (node (ref "R128") (pin "1") (pinfunction "1_1") (pintype "passive"))
    )
    (net (code "68") (name "/OUT_DIGIO3") (class "Default")
      (node (ref "J22") (pin "12") (pinfunction "P12_12") (pintype "passive"))
      (node (ref "R129") (pin "1") (pinfunction "1_1") (pintype "passive"))
    )
    (net (code "69") (name "/OUT_DIGIO4") (class "Default")
      (node (ref "J22") (pin "15") (pinfunction "P15_15") (pintype "passive"))
      (node (ref "R130") (pin "1") (pinfunction "1_1") (pintype "passive"))
    )
    (net (code "70") (name "/OUT_DIGIO5") (class "Default")
      (node (ref "J22") (pin "18") (pinfunction "P18_18") (pintype "passive"))
      (node (ref "R131") (pin "1") (pinfunction "1_1") (pintype "passive"))
    )
    (net (code "71") (name "/OUT_DIGIO6") (class "Default")
      (node (ref "J22") (pin "21") (pinfunction "P21_21") (pintype "passive"))
      (node (ref "R133") (pin "1") (pinfunction "1_1") (pintype "passive"))
    )
    (net (code "72") (name "/OUT_DIGIO7") (class "Default")
      (node (ref "J22") (pin "24") (pinfunction "P24_24") (pintype "passive"))
      (node (ref "R134") (pin "1") (pinfunction "1_1") (pintype "passive"))
    )
    (net (code "73") (name "/OUT_DIGIO8") (class "Default")
      (node (ref "J23") (pin "3") (pinfunction "3_3") (pintype "passive"))
      (node (ref "R135") (pin "1") (pinfunction "1_1") (pintype "passive"))
    )
    (net (code "74") (name "/OUT_DIGIO9") (class "Default")
      (node (ref "J23") (pin "6") (pinfunction "P6_6") (pintype "passive"))
      (node (ref "R136") (pin "1") (pinfunction "1_1") (pintype "passive"))
    )
    (net (code "75") (name "/OUT_DIGIO10") (class "Default")
      (node (ref "J23") (pin "9") (pinfunction "P9_9") (pintype "passive"))
      (node (ref "R137") (pin "1") (pinfunction "1_1") (pintype "passive"))
    )
    (net (code "76") (name "/OUT_DIGIO11") (class "Default")
      (node (ref "J23") (pin "12") (pinfunction "P12_12") (pintype "passive"))
      (node (ref "R138") (pin "1") (pinfunction "1_1") (pintype "passive"))
    )
    (net (code "77") (name "/OUT_DIGIO12") (class "Default")
      (node (ref "J23") (pin "15") (pinfunction "P15_15") (pintype "passive"))
      (node (ref "R139") (pin "1") (pinfunction "1_1") (pintype "passive"))
    )
    (net (code "78") (name "/OUT_DIGIO13") (class "Default")
      (node (ref "J23") (pin "18") (pinfunction "P18_18") (pintype "passive"))
      (node (ref "R140") (pin "1") (pinfunction "1_1") (pintype "passive"))
    )
    (net (code "79") (name "/OUT_DIGIO14") (class "Default")
      (node (ref "J23") (pin "21") (pinfunction "P21_21") (pintype "passive"))
      (node (ref "R141") (pin "1") (pinfunction "1_1") (pintype "passive"))
    )
    (net (code "80") (name "/OUT_DIGIO15") (class "Default")
      (node (ref "J23") (pin "24") (pinfunction "P24_24") (pintype "passive"))
      (node (ref "R150") (pin "1") (pinfunction "1_1") (pintype "passive"))
    )
    (net (code "81") (name "/OUT_DIGIO16") (class "Default")
      (node (ref "J24") (pin "3") (pinfunction "3_3") (pintype "passive"))
      (node (ref "R151") (pin "1") (pinfunction "1_1") (pintype "passive"))
    )
    (net (code "82") (name "/OUT_DIGIO17") (class "Default")
      (node (ref "J24") (pin "6") (pinfunction "P6_6") (pintype "passive"))
      (node (ref "R152") (pin "1") (pinfunction "1_1") (pintype "passive"))
    )
    (net (code "83") (name "/OUT_DIGIO18") (class "Default")
      (node (ref "J24") (pin "9") (pinfunction "P9_9") (pintype "passive"))
      (node (ref "R153") (pin "1") (pinfunction "1_1") (pintype "passive"))
    )
    (net (code "84") (name "/OUT_DIGIO19") (class "Default")
      (node (ref "J24") (pin "12") (pinfunction "P12_12") (pintype "passive"))
      (node (ref "R155") (pin "1") (pinfunction "1_1") (pintype "passive"))
    )
    (net (code "85") (name "/OUT_DIGIO20") (class "Default")
      (node (ref "J24") (pin "15") (pinfunction "P15_15") (pintype "passive"))
      (node (ref "R156") (pin "1") (pinfunction "1_1") (pintype "passive"))
    )
    (net (code "86") (name "/OUT_DIGIO21") (class "Default")
      (node (ref "J24") (pin "18") (pinfunction "P18_18") (pintype "passive"))
      (node (ref "R157") (pin "1") (pinfunction "1_1") (pintype "passive"))
    )
    (net (code "87") (name "/OUT_DIGIO22") (class "Default")
      (node (ref "J24") (pin "21") (pinfunction "P21_21") (pintype "passive"))
      (node (ref "R158") (pin "1") (pinfunction "1_1") (pintype "passive"))
    )
    (net (code "88") (name "/OUT_DIGIO23") (class "Default")
      (node (ref "J24") (pin "24") (pinfunction "P24_24") (pintype "passive"))
      (node (ref "R159") (pin "1") (pinfunction "1_1") (pintype "passive"))
    )
    (net (code "89") (name "/OUT_DIGIO24") (class "Default")
      (node (ref "J25") (pin "3") (pinfunction "3_3") (pintype "passive"))
      (node (ref "R160") (pin "1") (pinfunction "1_1") (pintype "passive"))
    )
    (net (code "90") (name "/OUT_DIGIO25") (class "Default")
      (node (ref "J25") (pin "6") (pinfunction "P6_6") (pintype "passive"))
      (node (ref "R161") (pin "1") (pinfunction "1_1") (pintype "passive"))
    )
    (net (code "91") (name "/OUT_DIGIO26") (class "Default")
      (node (ref "J25") (pin "9") (pinfunction "P9_9") (pintype "passive"))
      (node (ref "R170") (pin "1") (pinfunction "1_1") (pintype "passive"))
    )
    (net (code "92") (name "/OUT_DIGIO27") (class "Default")
      (node (ref "J25") (pin "12") (pinfunction "P12_12") (pintype "passive"))
      (node (ref "R171") (pin "1") (pinfunction "1_1") (pintype "passive"))
    )
    (net (code "93") (name "/OUT_DIGIO28") (class "Default")
      (node (ref "J25") (pin "15") (pinfunction "P15_15") (pintype "passive"))
      (node (ref "R172") (pin "1") (pinfunction "1_1") (pintype "passive"))
    )
    (net (code "94") (name "/OUT_DIGIO29") (class "Default")
      (node (ref "J25") (pin "18") (pinfunction "P18_18") (pintype "passive"))
      (node (ref "R173") (pin "1") (pinfunction "1_1") (pintype "passive"))
    )
    (net (code "95") (name "/OUT_DIGIO30") (class "Default")
      (node (ref "J25") (pin "21") (pinfunction "P21_21") (pintype "passive"))
      (node (ref "R175") (pin "1") (pinfunction "1_1") (pintype "passive"))
    )
    (net (code "96") (name "/OUT_DIGIO31") (class "Default")
      (node (ref "J25") (pin "24") (pinfunction "P24_24") (pintype "passive"))
      (node (ref "R176") (pin "1") (pinfunction "1_1") (pintype "passive"))
    )
    (net (code "97") (name "3V3") (class "Default")
      (node (ref "R120") (pin "2") (pinfunction "2_2") (pintype "passive"))
      (node (ref "R121") (pin "2") (pinfunction "2_2") (pintype "passive"))
      (node (ref "R122") (pin "2") (pinfunction "2_2") (pintype "passive"))
      (node (ref "R123") (pin "2") (pinfunction "2_2") (pintype "passive"))
      (node (ref "R124") (pin "2") (pinfunction "2_2") (pintype "passive"))
      (node (ref "R125") (pin "2") (pinfunction "2_2") (pintype "passive"))
      (node (ref "R126") (pin "2") (pinfunction "2_2") (pintype "passive"))
      (node (ref "R127") (pin "2") (pinfunction "2_2") (pintype "passive"))
      (node (ref "R142") (pin "2") (pinfunction "2_2") (pintype "passive"))
      (node (ref "R143") (pin "2") (pinfunction "2_2") (pintype "passive"))
      (node (ref "R144") (pin "2") (pinfunction "2_2") (pintype "passive"))
      (node (ref "R145") (pin "2") (pinfunction "2_2") (pintype "passive"))
      (node (ref "R146") (pin "2") (pinfunction "2_2") (pintype "passive"))
      (node (ref "R147") (pin "2") (pinfunction "2_2") (pintype "passive"))
      (node (ref "R148") (pin "2") (pinfunction "2_2") (pintype "passive"))
      (node (ref "R149") (pin "2") (pinfunction "2_2") (pintype "passive"))
      (node (ref "R162") (pin "2") (pinfunction "2_2") (pintype "passive"))
      (node (ref "R163") (pin "2") (pinfunction "2_2") (pintype "passive"))
      (node (ref "R164") (pin "2") (pinfunction "2_2") (pintype "passive"))
      (node (ref "R165") (pin "2") (pinfunction "2_2") (pintype "passive"))
      (node (ref "R166") (pin "2") (pinfunction "2_2") (pintype "passive"))
      (node (ref "R167") (pin "2") (pinfunction "2_2") (pintype "passive"))
      (node (ref "R168") (pin "2") (pinfunction "2_2") (pintype "passive"))
      (node (ref "R169") (pin "2") (pinfunction "2_2") (pintype "passive"))
      (node (ref "R177") (pin "2") (pinfunction "2_2") (pintype "passive"))
      (node (ref "R178") (pin "2") (pinfunction "2_2") (pintype "passive"))
      (node (ref "R179") (pin "2") (pinfunction "2_2") (pintype "passive"))
      (node (ref "R180") (pin "2") (pinfunction "2_2") (pintype "passive"))
      (node (ref "R181") (pin "2") (pinfunction "2_2") (pintype "passive"))
      (node (ref "R182") (pin "2") (pinfunction "2_2") (pintype "passive"))
      (node (ref "R183") (pin "2") (pinfunction "2_2") (pintype "passive"))
      (node (ref "R184") (pin "2") (pinfunction "2_2") (pintype "passive"))
    )
    (net (code "98") (name "GND") (class "Default")
      (node (ref "D10") (pin "2") (pinfunction "K_2") (pintype "passive"))
      (node (ref "D11") (pin "2") (pinfunction "K_2") (pintype "passive"))
      (node (ref "D12") (pin "2") (pinfunction "K_2") (pintype "passive"))
      (node (ref "D13") (pin "2") (pinfunction "K_2") (pintype "passive"))
      (node (ref "D14") (pin "2") (pinfunction "K_2") (pintype "passive"))
      (node (ref "D15") (pin "2") (pinfunction "K_2") (pintype "passive"))
      (node (ref "D16") (pin "2") (pinfunction "K_2") (pintype "passive"))
      (node (ref "D17") (pin "2") (pinfunction "K_2") (pintype "passive"))
      (node (ref "D18") (pin "2") (pinfunction "K_2") (pintype "passive"))
      (node (ref "D19") (pin "2") (pinfunction "K_2") (pintype "passive"))
      (node (ref "D20") (pin "2") (pinfunction "K_2") (pintype "passive"))
      (node (ref "D21") (pin "2") (pinfunction "K_2") (pintype "passive"))
      (node (ref "D22") (pin "2") (pinfunction "K_2") (pintype "passive"))
      (node (ref "D23") (pin "2") (pinfunction "K_2") (pintype "passive"))
      (node (ref "D24") (pin "2") (pinfunction "K_2") (pintype "passive"))
      (node (ref "D25") (pin "2") (pinfunction "K_2") (pintype "passive"))
      (node (ref "D26") (pin "2") (pinfunction "K_2") (pintype "passive"))
      (node (ref "D27") (pin "2") (pinfunction "K_2") (pintype "passive"))
      (node (ref "D28") (pin "2") (pinfunction "K_2") (pintype "passive"))
      (node (ref "D29") (pin "2") (pinfunction "K_2") (pintype "passive"))
      (node (ref "D30") (pin "2") (pinfunction "K_2") (pintype "passive"))
      (node (ref "D31") (pin "2") (pinfunction "K_2") (pintype "passive"))
      (node (ref "D32") (pin "2") (pinfunction "K_2") (pintype "passive"))
      (node (ref "D33") (pin "2") (pinfunction "K_2") (pintype "passive"))
      (node (ref "D34") (pin "2") (pinfunction "K_2") (pintype "passive"))
      (node (ref "D35") (pin "2") (pinfunction "K_2") (pintype "passive"))
      (node (ref "D36") (pin "2") (pinfunction "K_2") (pintype "passive"))
      (node (ref "D37") (pin "2") (pinfunction "K_2") (pintype "passive"))
      (node (ref "D6") (pin "2") (pinfunction "K_2") (pintype "passive"))
      (node (ref "D7") (pin "2") (pinfunction "K_2") (pintype "passive"))
      (node (ref "D8") (pin "2") (pinfunction "K_2") (pintype "passive"))
      (node (ref "D9") (pin "2") (pinfunction "K_2") (pintype "passive"))
      (node (ref "R132") (pin "1") (pinfunction "1_1") (pintype "passive"))
      (node (ref "R154") (pin "1") (pinfunction "1_1") (pintype "passive"))
      (node (ref "R174") (pin "1") (pinfunction "1_1") (pintype "passive"))
      (node (ref "R185") (pin "1") (pinfunction "1_1") (pintype "passive"))
    )
    (net (code "99") (name "Net-(D6-A)") (class "Default")
      (node (ref "D6") (pin "1") (pinfunction "A_1") (pintype "passive"))
      (node (ref "R118") (pin "2") (pinfunction "2_2") (pintype "passive"))
    )
    (net (code "100") (name "Net-(D7-A)") (class "Default")
      (node (ref "D7") (pin "1") (pinfunction "A_1") (pintype "passive"))
      (node (ref "R119") (pin "2") (pinfunction "2_2") (pintype "passive"))
    )
    (net (code "101") (name "Net-(D8-A)") (class "Default")
      (node (ref "D8") (pin "1") (pinfunction "A_1") (pintype "passive"))
      (node (ref "R128") (pin "2") (pinfunction "2_2") (pintype "passive"))
    )
    (net (code "102") (name "Net-(D9-A)") (class "Default")
      (node (ref "D9") (pin "1") (pinfunction "A_1") (pintype "passive"))
      (node (ref "R129") (pin "2") (pinfunction "2_2") (pintype "passive"))
    )
    (net (code "103") (name "Net-(D10-A)") (class "Default")
      (node (ref "D10") (pin "1") (pinfunction "A_1") (pintype "passive"))
      (node (ref "R130") (pin "2") (pinfunction "2_2") (pintype "passive"))
    )
    (net (code "104") (name "Net-(D11-A)") (class "Default")
      (node (ref "D11") (pin "1") (pinfunction "A_1") (pintype "passive"))
      (node (ref "R131") (pin "2") (pinfunction "2_2") (pintype "passive"))
    )
    (net (code "105") (name "Net-(D12-A)") (class "Default")
      (node (ref "D12") (pin "1") (pinfunction "A_1") (pintype "passive"))
      (node (ref "R133") (pin "2") (pinfunction "2_2") (pintype "passive"))
    )
    (net (code "106") (name "Net-(D13-A)") (class "Default")
      (node (ref "D13") (pin "1") (pinfunction "A_1") (pintype "passive"))
      (node (ref "R134") (pin "2") (pinfunction "2_2") (pintype "passive"))
    )
    (net (code "107") (name "Net-(D14-A)") (class "Default")
      (node (ref "D14") (pin "1") (pinfunction "A_1") (pintype "passive"))
      (node (ref "R135") (pin "2") (pinfunction "2_2") (pintype "passive"))
    )
    (net (code "108") (name "Net-(D15-A)") (class "Default")
      (node (ref "D15") (pin "1") (pinfunction "A_1") (pintype "passive"))
      (node (ref "R136") (pin "2") (pinfunction "2_2") (pintype "passive"))
    )
    (net (code "109") (name "Net-(D16-A)") (class "Default")
      (node (ref "D16") (pin "1") (pinfunction "A_1") (pintype "passive"))
      (node (ref "R137") (pin "2") (pinfunction "2_2") (pintype "passive"))
    )
    (net (code "110") (name "Net-(D17-A)") (class "Default")
      (node (ref "D17") (pin "1") (pinfunction "A_1") (pintype "passive"))
      (node (ref "R138") (pin "2") (pinfunction "2_2") (pintype "passive"))
    )
    (net (code "111") (name "Net-(D18-A)") (class "Default")
      (node (ref "D18") (pin "1") (pinfunction "A_1") (pintype "passive"))
      (node (ref "R139") (pin "2") (pinfunction "2_2") (pintype "passive"))
    )
    (net (code "112") (name "Net-(D19-A)") (class "Default")
      (node (ref "D19") (pin "1") (pinfunction "A_1") (pintype "passive"))
      (node (ref "R140") (pin "2") (pinfunction "2_2") (pintype "passive"))
    )
    (net (code "113") (name "Net-(D20-A)") (class "Default")
      (node (ref "D20") (pin "1") (pinfunction "A_1") (pintype "passive"))
      (node (ref "R141") (pin "2") (pinfunction "2_2") (pintype "passive"))
    )
    (net (code "114") (name "Net-(D21-A)") (class "Default")
      (node (ref "D21") (pin "1") (pinfunction "A_1") (pintype "passive"))
      (node (ref "R150") (pin "2") (pinfunction "2_2") (pintype "passive"))
    )
    (net (code "115") (name "Net-(D22-A)") (class "Default")
      (node (ref "D22") (pin "1") (pinfunction "A_1") (pintype "passive"))
      (node (ref "R151") (pin "2") (pinfunction "2_2") (pintype "passive"))
    )
    (net (code "116") (name "Net-(D23-A)") (class "Default")
      (node (ref "D23") (pin "1") (pinfunction "A_1") (pintype "passive"))
      (node (ref "R152") (pin "2") (pinfunction "2_2") (pintype "passive"))
    )
    (net (code "117") (name "Net-(D24-A)") (class "Default")
      (node (ref "D24") (pin "1") (pinfunction "A_1") (pintype "passive"))
      (node (ref "R153") (pin "2") (pinfunction "2_2") (pintype "passive"))
    )
    (net (code "118") (name "Net-(D25-A)") (class "Default")
      (node (ref "D25") (pin "1") (pinfunction "A_1") (pintype "passive"))
      (node (ref "R155") (pin "2") (pinfunction "2_2") (pintype "passive"))
    )
    (net (code "119") (name "Net-(D26-A)") (class "Default")
      (node (ref "D26") (pin "1") (pinfunction "A_1") (pintype "passive"))
      (node (ref "R156") (pin "2") (pinfunction "2_2") (pintype "passive"))
    )
    (net (code "120") (name "Net-(D27-A)") (class "Default")
      (node (ref "D27") (pin "1") (pinfunction "A_1") (pintype "passive"))
      (node (ref "R157") (pin "2") (pinfunction "2_2") (pintype "passive"))
    )
    (net (code "121") (name "Net-(D28-A)") (class "Default")
      (node (ref "D28") (pin "1") (pinfunction "A_1") (pintype "passive"))
      (node (ref "R158") (pin "2") (pinfunction "2_2") (pintype "passive"))
    )
    (net (code "122") (name "Net-(D29-A)") (class "Default")
      (node (ref "D29") (pin "1") (pinfunction "A_1") (pintype "passive"))
      (node (ref "R159") (pin "2") (pinfunction "2_2") (pintype "passive"))
    )
    (net (code "123") (name "Net-(D30-A)") (class "Default")
      (node (ref "D30") (pin "1") (pinfunction "A_1") (pintype "passive"))
      (node (ref "R160") (pin "2") (pinfunction "2_2") (pintype "passive"))
    )
    (net (code "124") (name "Net-(D31-A)") (class "Default")
      (node (ref "D31") (pin "1") (pinfunction "A_1") (pintype "passive"))
      (node (ref "R161") (pin "2") (pinfunction "2_2") (pintype "passive"))
    )
    (net (code "125") (name "Net-(D32-A)") (class "Default")
      (node (ref "D32") (pin "1") (pinfunction "A_1") (pintype "passive"))
      (node (ref "R170") (pin "2") (pinfunction "2_2") (pintype "passive"))
    )
    (net (code "126") (name "Net-(D33-A)") (class "Default")
      (node (ref "D33") (pin "1") (pinfunction "A_1") (pintype "passive"))
      (node (ref "R171") (pin "2") (pinfunction "2_2") (pintype "passive"))
    )
    (net (code "127") (name "Net-(D34-A)") (class "Default")
      (node (ref "D34") (pin "1") (pinfunction "A_1") (pintype "passive"))
      (node (ref "R172") (pin "2") (pinfunction "2_2") (pintype "passive"))
    )
    (net (code "128") (name "Net-(D35-A)") (class "Default")
      (node (ref "D35") (pin "1") (pinfunction "A_1") (pintype "passive"))
      (node (ref "R173") (pin "2") (pinfunction "2_2") (pintype "passive"))
    )
    (net (code "129") (name "Net-(D36-A)") (class "Default")
      (node (ref "D36") (pin "1") (pinfunction "A_1") (pintype "passive"))
      (node (ref "R175") (pin "2") (pinfunction "2_2") (pintype "passive"))
    )
    (net (code "130") (name "Net-(D37-A)") (class "Default")
      (node (ref "D37") (pin "1") (pinfunction "A_1") (pintype "passive"))
      (node (ref "R176") (pin "2") (pinfunction "2_2") (pintype "passive"))
    )
    (net (code "131") (name "Net-(R132-Pad2)") (class "Default")
      (node (ref "R132") (pin "2") (pinfunction "2_2") (pintype "passive"))
      (node (ref "SW4") (pin "10") (pinfunction "10_10") (pintype "passive"))
      (node (ref "SW4") (pin "11") (pinfunction "11_11") (pintype "passive"))
      (node (ref "SW4") (pin "12") (pinfunction "12_12") (pintype "passive"))
      (node (ref "SW4") (pin "13") (pinfunction "13_13") (pintype "passive"))
      (node (ref "SW4") (pin "14") (pinfunction "14_14") (pintype "passive"))
      (node (ref "SW4") (pin "15") (pinfunction "15_15") (pintype "passive"))
      (node (ref "SW4") (pin "16") (pinfunction "16_16") (pintype "passive"))
      (node (ref "SW4") (pin "9") (pinfunction "9_9") (pintype "passive"))
    )
    (net (code "132") (name "Net-(R154-Pad2)") (class "Default")
      (node (ref "R154") (pin "2") (pinfunction "2_2") (pintype "passive"))
      (node (ref "SW5") (pin "10") (pinfunction "10_10") (pintype "passive"))
      (node (ref "SW5") (pin "11") (pinfunction "11_11") (pintype "passive"))
      (node (ref "SW5") (pin "12") (pinfunction "12_12") (pintype "passive"))
      (node (ref "SW5") (pin "13") (pinfunction "13_13") (pintype "passive"))
      (node (ref "SW5") (pin "14") (pinfunction "14_14") (pintype "passive"))
      (node (ref "SW5") (pin "15") (pinfunction "15_15") (pintype "passive"))
      (node (ref "SW5") (pin "16") (pinfunction "16_16") (pintype "passive"))
      (node (ref "SW5") (pin "9") (pinfunction "9_9") (pintype "passive"))
    )
    (net (code "133") (name "Net-(R174-Pad2)") (class "Default")
      (node (ref "R174") (pin "2") (pinfunction "2_2") (pintype "passive"))
      (node (ref "SW6") (pin "10") (pinfunction "10_10") (pintype "passive"))
      (node (ref "SW6") (pin "11") (pinfunction "11_11") (pintype "passive"))
      (node (ref "SW6") (pin "12") (pinfunction "12_12") (pintype "passive"))
      (node (ref "SW6") (pin "13") (pinfunction "13_13") (pintype "passive"))
      (node (ref "SW6") (pin "14") (pinfunction "14_14") (pintype "passive"))
      (node (ref "SW6") (pin "15") (pinfunction "15_15") (pintype "passive"))
      (node (ref "SW6") (pin "16") (pinfunction "16_16") (pintype "passive"))
      (node (ref "SW6") (pin "9") (pinfunction "9_9") (pintype "passive"))
    )
    (net (code "134") (name "Net-(R185-Pad2)") (class "Default")
      (node (ref "R185") (pin "2") (pinfunction "2_2") (pintype "passive"))
      (node (ref "SW7") (pin "10") (pinfunction "10_10") (pintype "passive"))
      (node (ref "SW7") (pin "11") (pinfunction "11_11") (pintype "passive"))
      (node (ref "SW7") (pin "12") (pinfunction "12_12") (pintype "passive"))
      (node (ref "SW7") (pin "13") (pinfunction "13_13") (pintype "passive"))
      (node (ref "SW7") (pin "14") (pinfunction "14_14") (pintype "passive"))
      (node (ref "SW7") (pin "15") (pinfunction "15_15") (pintype "passive"))
      (node (ref "SW7") (pin "16") (pinfunction "16_16") (pintype "passive"))
      (node (ref "SW7") (pin "9") (pinfunction "9_9") (pintype "passive"))
    )
  )
)
